# SuperPro-res-moved.net
KiCad netlist of a schematic drawn in EAGLE
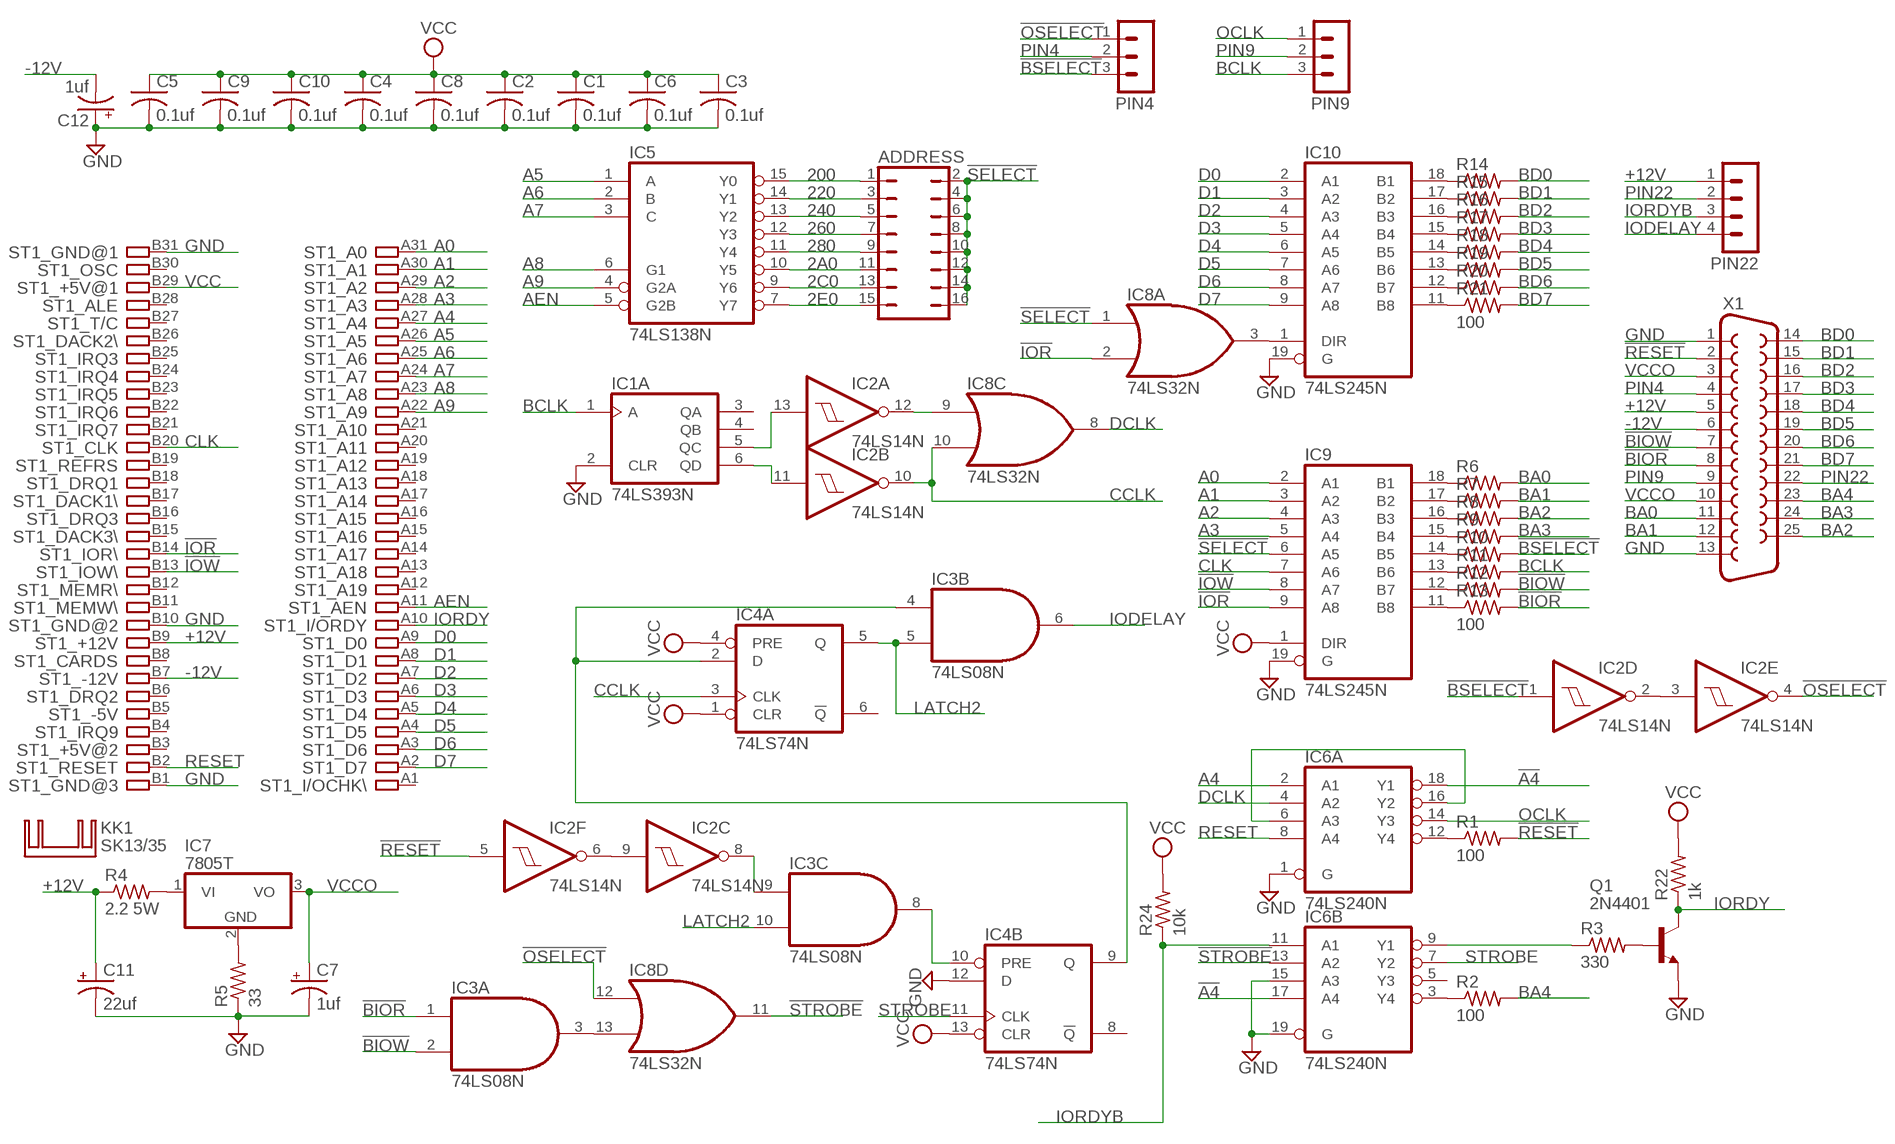
[diagram p0: schematic, sheet 1]

(export (version "E")
  (design (tool "Eeschema 10.0.6"))
  (components
    (comp (ref "ADDRESS")
      (value "JP8Q")
      (footprint "eagle-import:JP8Q")
      (libsource (lib "eagle-import") (part "JP8Q"))
    )
    (comp (ref "C1")
      (value "0.1uf")
      (footprint "eagle-import:C050-025X075")
      (libsource (lib "eagle-import") (part "C-US050-025X075"))
    )
    (comp (ref "C2")
      (value "0.1uf")
      (footprint "eagle-import:C050-025X075")
      (libsource (lib "eagle-import") (part "C-US050-025X075"))
    )
    (comp (ref "C3")
      (value "0.1uf")
      (footprint "eagle-import:C050-025X075")
      (libsource (lib "eagle-import") (part "C-US050-025X075"))
    )
    (comp (ref "C4")
      (value "0.1uf")
      (footprint "eagle-import:C050-025X075")
      (libsource (lib "eagle-import") (part "C-US050-025X075"))
    )
    (comp (ref "C5")
      (value "0.1uf")
      (footprint "eagle-import:C050-025X075")
      (libsource (lib "eagle-import") (part "C-US050-025X075"))
    )
    (comp (ref "C6")
      (value "0.1uf")
      (footprint "eagle-import:C050-025X075")
      (libsource (lib "eagle-import") (part "C-US050-025X075"))
    )
    (comp (ref "C7")
      (value "1uf")
      (footprint "eagle-import:E5-10,5")
      (libsource (lib "eagle-import") (part "CPOL-USE5-10.5"))
    )
    (comp (ref "C8")
      (value "0.1uf")
      (footprint "eagle-import:C050-025X075")
      (libsource (lib "eagle-import") (part "C-US050-025X075"))
    )
    (comp (ref "C9")
      (value "0.1uf")
      (footprint "eagle-import:C050-025X075")
      (libsource (lib "eagle-import") (part "C-US050-025X075"))
    )
    (comp (ref "C10")
      (value "0.1uf")
      (footprint "eagle-import:C050-025X075")
      (libsource (lib "eagle-import") (part "C-US050-025X075"))
    )
    (comp (ref "C11")
      (value "22uf")
      (footprint "eagle-import:E5-10,5")
      (libsource (lib "eagle-import") (part "CPOL-USE5-10.5"))
    )
    (comp (ref "C12")
      (value "1uf")
      (footprint "eagle-import:E5-10,5")
      (libsource (lib "eagle-import") (part "CPOL-USE5-10.5"))
    )
    (comp (ref "IC1")
      (value "74LS393N")
      (footprint "eagle-import:DIL14")
      (libsource (lib "eagle-import") (part "74393NLS"))
    )
    (comp (ref "IC2")
      (value "74LS14N")
      (footprint "eagle-import:DIL14")
      (libsource (lib "eagle-import") (part "7414NLS"))
    )
    (comp (ref "IC3")
      (value "74LS08N")
      (footprint "eagle-import:DIL14")
      (libsource (lib "eagle-import") (part "7408NLS"))
    )
    (comp (ref "IC4")
      (value "74LS74N")
      (footprint "eagle-import:DIL14")
      (libsource (lib "eagle-import") (part "7474NLS"))
    )
    (comp (ref "IC5")
      (value "74LS138N")
      (footprint "eagle-import:DIL16")
      (libsource (lib "eagle-import") (part "74138NLS"))
    )
    (comp (ref "IC6")
      (value "74LS240N")
      (footprint "eagle-import:DIL20")
      (libsource (lib "eagle-import") (part "74240NLS"))
    )
    (comp (ref "IC7")
      (value "7805T")
      (footprint "eagle-import:TO220H")
      (libsource (lib "eagle-import") (part "78T05"))
    )
    (comp (ref "IC8")
      (value "74LS32N")
      (footprint "eagle-import:DIL14")
      (libsource (lib "eagle-import") (part "7432NLS"))
    )
    (comp (ref "IC9")
      (value "74LS245N")
      (footprint "eagle-import:DIL20")
      (libsource (lib "eagle-import") (part "74245NLS"))
    )
    (comp (ref "IC10")
      (value "74LS245N")
      (footprint "eagle-import:DIL20")
      (libsource (lib "eagle-import") (part "74245NLS"))
    )
    (comp (ref "KK1")
      (value "SK13/35")
      (footprint "eagle-import:SK13_35")
      (libsource (lib "eagle-import") (part "SK13/35"))
    )
    (comp (ref "PIN4")
      (value "MA03-1")
      (footprint "eagle-import:MA03-1")
      (libsource (lib "eagle-import") (part "MA03-1"))
    )
    (comp (ref "PIN9")
      (value "MA03-1")
      (footprint "eagle-import:MA03-1")
      (libsource (lib "eagle-import") (part "MA03-1"))
    )
    (comp (ref "PIN22")
      (value "MA04-1")
      (footprint "eagle-import:MA04-1")
      (libsource (lib "eagle-import") (part "MA04-1"))
    )
    (comp (ref "Q1")
      (value "2N4401")
      (footprint "eagle-import:TO92")
      (libsource (lib "eagle-import") (part "2N4416"))
    )
    (comp (ref "R1")
      (value "100")
      (footprint "eagle-import:0207_10")
      (libsource (lib "eagle-import") (part "R-US_0207/10"))
    )
    (comp (ref "R2")
      (value "100")
      (footprint "eagle-import:0207_10")
      (libsource (lib "eagle-import") (part "R-US_0207/10"))
    )
    (comp (ref "R3")
      (value "330")
      (footprint "eagle-import:0207_10")
      (libsource (lib "eagle-import") (part "R-US_0207/10"))
    )
    (comp (ref "R4")
      (value "2.2 5W")
      (footprint "eagle-import:0922_22")
      (libsource (lib "eagle-import") (part "R-US_0922/22"))
    )
    (comp (ref "R5")
      (value "33")
      (footprint "eagle-import:0207_10")
      (libsource (lib "eagle-import") (part "R-US_0207/10"))
    )
    (comp (ref "R6")
      (value "R-US_0207/10")
      (footprint "eagle-import:0207_10")
      (libsource (lib "eagle-import") (part "R-US_0207/10"))
    )
    (comp (ref "R7")
      (value "R-US_0207/10")
      (footprint "eagle-import:0207_10")
      (libsource (lib "eagle-import") (part "R-US_0207/10"))
    )
    (comp (ref "R8")
      (value "R-US_0207/10")
      (footprint "eagle-import:0207_10")
      (libsource (lib "eagle-import") (part "R-US_0207/10"))
    )
    (comp (ref "R9")
      (value "R-US_0207/10")
      (footprint "eagle-import:0207_10")
      (libsource (lib "eagle-import") (part "R-US_0207/10"))
    )
    (comp (ref "R10")
      (value "R-US_0207/10")
      (footprint "eagle-import:0207_10")
      (libsource (lib "eagle-import") (part "R-US_0207/10"))
    )
    (comp (ref "R11")
      (value "R-US_0207/10")
      (footprint "eagle-import:0207_10")
      (libsource (lib "eagle-import") (part "R-US_0207/10"))
    )
    (comp (ref "R12")
      (value "R-US_0207/10")
      (footprint "eagle-import:0207_10")
      (libsource (lib "eagle-import") (part "R-US_0207/10"))
    )
    (comp (ref "R13")
      (value "100")
      (footprint "eagle-import:0207_10")
      (libsource (lib "eagle-import") (part "R-US_0207/10"))
    )
    (comp (ref "R14")
      (value "R-US_0207/10")
      (footprint "eagle-import:0207_10")
      (libsource (lib "eagle-import") (part "R-US_0207/10"))
    )
    (comp (ref "R15")
      (value "R-US_0207/10")
      (footprint "eagle-import:0207_10")
      (libsource (lib "eagle-import") (part "R-US_0207/10"))
    )
    (comp (ref "R16")
      (value "R-US_0207/10")
      (footprint "eagle-import:0207_10")
      (libsource (lib "eagle-import") (part "R-US_0207/10"))
    )
    (comp (ref "R17")
      (value "R-US_0207/10")
      (footprint "eagle-import:0207_10")
      (libsource (lib "eagle-import") (part "R-US_0207/10"))
    )
    (comp (ref "R18")
      (value "R-US_0207/10")
      (footprint "eagle-import:0207_10")
      (libsource (lib "eagle-import") (part "R-US_0207/10"))
    )
    (comp (ref "R19")
      (value "R-US_0207/10")
      (footprint "eagle-import:0207_10")
      (libsource (lib "eagle-import") (part "R-US_0207/10"))
    )
    (comp (ref "R20")
      (value "R-US_0207/10")
      (footprint "eagle-import:0207_10")
      (libsource (lib "eagle-import") (part "R-US_0207/10"))
    )
    (comp (ref "R21")
      (value "100")
      (footprint "eagle-import:0207_10")
      (libsource (lib "eagle-import") (part "R-US_0207/10"))
    )
    (comp (ref "R22")
      (value "1k")
      (footprint "eagle-import:0207_10")
      (libsource (lib "eagle-import") (part "R-US_0207/10"))
    )
    (comp (ref "R24")
      (value "10k")
      (footprint "eagle-import:0207_10")
      (libsource (lib "eagle-import") (part "R-US_0207/10"))
    )
    (comp (ref "ST1")
      (value "IBM8BIT")
      (footprint "eagle-import:IBM8BIT")
      (libsource (lib "eagle-import") (part "IBM8BIT"))
    )
    (comp (ref "X1")
      (value "F25H")
      (footprint "eagle-import:F25H")
      (libsource (lib "eagle-import") (part "F25H"))
    )
  )
  (nets
    (net (code "1") (name "/+12V") (class "Default")
      (node (ref "C11") (pin "+") (pinfunction "+_+") (pintype "passive"))
      (node (ref "PIN22") (pin "1") (pinfunction "1_1") (pintype "passive"))
      (node (ref "R4") (pin "1") (pinfunction "1_1") (pintype "passive"))
      (node (ref "ST1") (pin "B9") (pinfunction "P_B9") (pintype "bidirectional"))
      (node (ref "X1") (pin "5") (pinfunction "5_5") (pintype "passive"))
    )
    (net (code "2") (name "/-12V") (class "Default")
      (node (ref "C12") (pin "-") (pinfunction "-_-") (pintype "passive"))
      (node (ref "ST1") (pin "B7") (pinfunction "P_B7") (pintype "bidirectional"))
      (node (ref "X1") (pin "6") (pinfunction "6_6") (pintype "passive"))
    )
    (net (code "3") (name "/2A0") (class "Default")
      (node (ref "ADDRESS") (pin "11") (pinfunction "11_11") (pintype "passive"))
      (node (ref "IC5") (pin "10") (pinfunction "Y5_10") (pintype "output"))
    )
    (net (code "4") (name "/2C0") (class "Default")
      (node (ref "ADDRESS") (pin "13") (pinfunction "13_13") (pintype "passive"))
      (node (ref "IC5") (pin "9") (pinfunction "Y6_9") (pintype "output"))
    )
    (net (code "5") (name "/2E0") (class "Default")
      (node (ref "ADDRESS") (pin "15") (pinfunction "15_15") (pintype "passive"))
      (node (ref "IC5") (pin "7") (pinfunction "Y7_7") (pintype "output"))
    )
    (net (code "6") (name "/200") (class "Default")
      (node (ref "ADDRESS") (pin "1") (pinfunction "1_1") (pintype "passive"))
      (node (ref "IC5") (pin "15") (pinfunction "Y0_15") (pintype "output"))
    )
    (net (code "7") (name "/220") (class "Default")
      (node (ref "ADDRESS") (pin "3") (pinfunction "3_3") (pintype "passive"))
      (node (ref "IC5") (pin "14") (pinfunction "Y1_14") (pintype "output"))
    )
    (net (code "8") (name "/240") (class "Default")
      (node (ref "ADDRESS") (pin "5") (pinfunction "5_5") (pintype "passive"))
      (node (ref "IC5") (pin "13") (pinfunction "Y2_13") (pintype "output"))
    )
    (net (code "9") (name "/260") (class "Default")
      (node (ref "ADDRESS") (pin "7") (pinfunction "7_7") (pintype "passive"))
      (node (ref "IC5") (pin "12") (pinfunction "Y3_12") (pintype "output"))
    )
    (net (code "10") (name "/280") (class "Default")
      (node (ref "ADDRESS") (pin "9") (pinfunction "9_9") (pintype "passive"))
      (node (ref "IC5") (pin "11") (pinfunction "Y4_11") (pintype "output"))
    )
    (net (code "11") (name "/A0") (class "Default")
      (node (ref "IC9") (pin "2") (pinfunction "A1_2") (pintype "bidirectional"))
      (node (ref "ST1") (pin "A31") (pinfunction "P_A31") (pintype "bidirectional"))
    )
    (net (code "12") (name "/A1") (class "Default")
      (node (ref "IC9") (pin "3") (pinfunction "A2_3") (pintype "bidirectional"))
      (node (ref "ST1") (pin "A30") (pinfunction "P_A30") (pintype "bidirectional"))
    )
    (net (code "13") (name "/A2") (class "Default")
      (node (ref "IC9") (pin "4") (pinfunction "A3_4") (pintype "bidirectional"))
      (node (ref "ST1") (pin "A29") (pinfunction "P_A29") (pintype "bidirectional"))
    )
    (net (code "14") (name "/A3") (class "Default")
      (node (ref "IC9") (pin "5") (pinfunction "A4_5") (pintype "bidirectional"))
      (node (ref "ST1") (pin "A28") (pinfunction "P_A28") (pintype "bidirectional"))
    )
    (net (code "15") (name "/A4") (class "Default")
      (node (ref "IC6") (pin "2") (pinfunction "A1_2") (pintype "input"))
      (node (ref "ST1") (pin "A27") (pinfunction "P_A27") (pintype "bidirectional"))
    )
    (net (code "16") (name "/A5") (class "Default")
      (node (ref "IC5") (pin "1") (pinfunction "A_1") (pintype "input"))
      (node (ref "ST1") (pin "A26") (pinfunction "P_A26") (pintype "bidirectional"))
    )
    (net (code "17") (name "/A6") (class "Default")
      (node (ref "IC5") (pin "2") (pinfunction "B_2") (pintype "input"))
      (node (ref "ST1") (pin "A25") (pinfunction "P_A25") (pintype "bidirectional"))
    )
    (net (code "18") (name "/A7") (class "Default")
      (node (ref "IC5") (pin "3") (pinfunction "C_3") (pintype "input"))
      (node (ref "ST1") (pin "A24") (pinfunction "P_A24") (pintype "bidirectional"))
    )
    (net (code "19") (name "/A8") (class "Default")
      (node (ref "IC5") (pin "6") (pinfunction "G1_6") (pintype "input"))
      (node (ref "ST1") (pin "A23") (pinfunction "P_A23") (pintype "bidirectional"))
    )
    (net (code "20") (name "/A9") (class "Default")
      (node (ref "IC5") (pin "4") (pinfunction "G2A_4") (pintype "input"))
      (node (ref "ST1") (pin "A22") (pinfunction "P_A22") (pintype "bidirectional"))
    )
    (net (code "21") (name "/AEN") (class "Default")
      (node (ref "IC5") (pin "5") (pinfunction "G2B_5") (pintype "input"))
      (node (ref "ST1") (pin "A11") (pinfunction "P_A11") (pintype "bidirectional"))
    )
    (net (code "22") (name "/BA0") (class "Default")
      (node (ref "R6") (pin "2") (pinfunction "2_2") (pintype "passive"))
      (node (ref "X1") (pin "11") (pinfunction "11_11") (pintype "passive"))
    )
    (net (code "23") (name "/BA1") (class "Default")
      (node (ref "R7") (pin "2") (pinfunction "2_2") (pintype "passive"))
      (node (ref "X1") (pin "12") (pinfunction "12_12") (pintype "passive"))
    )
    (net (code "24") (name "/BA2") (class "Default")
      (node (ref "R8") (pin "2") (pinfunction "2_2") (pintype "passive"))
      (node (ref "X1") (pin "25") (pinfunction "25_25") (pintype "passive"))
    )
    (net (code "25") (name "/BA3") (class "Default")
      (node (ref "R9") (pin "2") (pinfunction "2_2") (pintype "passive"))
      (node (ref "X1") (pin "24") (pinfunction "24_24") (pintype "passive"))
    )
    (net (code "26") (name "/BA4") (class "Default")
      (node (ref "R2") (pin "2") (pinfunction "2_2") (pintype "passive"))
      (node (ref "X1") (pin "23") (pinfunction "23_23") (pintype "passive"))
    )
    (net (code "27") (name "/BCLK") (class "Default")
      (node (ref "IC1") (pin "1") (pinfunction "A_1") (pintype "input"))
      (node (ref "PIN9") (pin "3") (pinfunction "3_3") (pintype "passive"))
      (node (ref "R11") (pin "2") (pinfunction "2_2") (pintype "passive"))
    )
    (net (code "28") (name "/BD0") (class "Default")
      (node (ref "R14") (pin "2") (pinfunction "2_2") (pintype "passive"))
      (node (ref "X1") (pin "14") (pinfunction "14_14") (pintype "passive"))
    )
    (net (code "29") (name "/BD1") (class "Default")
      (node (ref "R15") (pin "2") (pinfunction "2_2") (pintype "passive"))
      (node (ref "X1") (pin "15") (pinfunction "15_15") (pintype "passive"))
    )
    (net (code "30") (name "/BD2") (class "Default")
      (node (ref "R16") (pin "2") (pinfunction "2_2") (pintype "passive"))
      (node (ref "X1") (pin "16") (pinfunction "16_16") (pintype "passive"))
    )
    (net (code "31") (name "/BD3") (class "Default")
      (node (ref "R17") (pin "2") (pinfunction "2_2") (pintype "passive"))
      (node (ref "X1") (pin "17") (pinfunction "17_17") (pintype "passive"))
    )
    (net (code "32") (name "/BD4") (class "Default")
      (node (ref "R18") (pin "2") (pinfunction "2_2") (pintype "passive"))
      (node (ref "X1") (pin "18") (pinfunction "18_18") (pintype "passive"))
    )
    (net (code "33") (name "/BD5") (class "Default")
      (node (ref "R19") (pin "2") (pinfunction "2_2") (pintype "passive"))
      (node (ref "X1") (pin "19") (pinfunction "19_19") (pintype "passive"))
    )
    (net (code "34") (name "/BD6") (class "Default")
      (node (ref "R20") (pin "2") (pinfunction "2_2") (pintype "passive"))
      (node (ref "X1") (pin "20") (pinfunction "20_20") (pintype "passive"))
    )
    (net (code "35") (name "/BD7") (class "Default")
      (node (ref "R21") (pin "2") (pinfunction "2_2") (pintype "passive"))
      (node (ref "X1") (pin "21") (pinfunction "21_21") (pintype "passive"))
    )
    (net (code "36") (name "/CCLK") (class "Default")
      (node (ref "IC2") (pin "10") (pinfunction "O_10") (pintype "output"))
      (node (ref "IC4") (pin "3") (pinfunction "CLK_3") (pintype "input"))
      (node (ref "IC8") (pin "10") (pinfunction "I1_10") (pintype "input"))
    )
    (net (code "37") (name "/CLK") (class "Default")
      (node (ref "IC9") (pin "7") (pinfunction "A6_7") (pintype "bidirectional"))
      (node (ref "ST1") (pin "B20") (pinfunction "P_B20") (pintype "bidirectional"))
    )
    (net (code "38") (name "/D0") (class "Default")
      (node (ref "IC10") (pin "2") (pinfunction "A1_2") (pintype "bidirectional"))
      (node (ref "ST1") (pin "A9") (pinfunction "P_A9") (pintype "bidirectional"))
    )
    (net (code "39") (name "/D1") (class "Default")
      (node (ref "IC10") (pin "3") (pinfunction "A2_3") (pintype "bidirectional"))
      (node (ref "ST1") (pin "A8") (pinfunction "P_A8") (pintype "bidirectional"))
    )
    (net (code "40") (name "/D2") (class "Default")
      (node (ref "IC10") (pin "4") (pinfunction "A3_4") (pintype "bidirectional"))
      (node (ref "ST1") (pin "A7") (pinfunction "P_A7") (pintype "bidirectional"))
    )
    (net (code "41") (name "/D3") (class "Default")
      (node (ref "IC10") (pin "5") (pinfunction "A4_5") (pintype "bidirectional"))
      (node (ref "ST1") (pin "A6") (pinfunction "P_A6") (pintype "bidirectional"))
    )
    (net (code "42") (name "/D4") (class "Default")
      (node (ref "IC10") (pin "6") (pinfunction "A5_6") (pintype "bidirectional"))
      (node (ref "ST1") (pin "A5") (pinfunction "P_A5") (pintype "bidirectional"))
    )
    (net (code "43") (name "/D5") (class "Default")
      (node (ref "IC10") (pin "7") (pinfunction "A6_7") (pintype "bidirectional"))
      (node (ref "ST1") (pin "A4") (pinfunction "P_A4") (pintype "bidirectional"))
    )
    (net (code "44") (name "/D6") (class "Default")
      (node (ref "IC10") (pin "8") (pinfunction "A7_8") (pintype "bidirectional"))
      (node (ref "ST1") (pin "A3") (pinfunction "P_A3") (pintype "bidirectional"))
    )
    (net (code "45") (name "/D7") (class "Default")
      (node (ref "IC10") (pin "9") (pinfunction "A8_9") (pintype "bidirectional"))
      (node (ref "ST1") (pin "A2") (pinfunction "P_A2") (pintype "bidirectional"))
    )
    (net (code "46") (name "/DCLK") (class "Default")
      (node (ref "IC6") (pin "4") (pinfunction "A2_4") (pintype "input"))
      (node (ref "IC8") (pin "8") (pinfunction "O_8") (pintype "output"))
    )
    (net (code "47") (name "/IODELAY") (class "Default")
      (node (ref "IC3") (pin "6") (pinfunction "O_6") (pintype "output"))
      (node (ref "PIN22") (pin "4") (pinfunction "4_4") (pintype "passive"))
    )
    (net (code "48") (name "/IORDY") (class "Default")
      (node (ref "Q1") (pin "1") (pinfunction "C_1") (pintype "passive"))
      (node (ref "R22") (pin "1") (pinfunction "1_1") (pintype "passive"))
      (node (ref "ST1") (pin "A10") (pinfunction "P_A10") (pintype "bidirectional"))
    )
    (net (code "49") (name "/IORDYB") (class "Default")
      (node (ref "IC6") (pin "11") (pinfunction "A1_11") (pintype "input"))
      (node (ref "PIN22") (pin "3") (pinfunction "3_3") (pintype "passive"))
      (node (ref "R24") (pin "1") (pinfunction "1_1") (pintype "passive"))
    )
    (net (code "50") (name "/LATCH2") (class "Default")
      (node (ref "IC3") (pin "10") (pinfunction "I1_10") (pintype "input"))
      (node (ref "IC3") (pin "5") (pinfunction "I1_5") (pintype "input"))
      (node (ref "IC4") (pin "5") (pinfunction "Q_5") (pintype "output"))
    )
    (net (code "51") (name "/OCLK") (class "Default")
      (node (ref "IC6") (pin "14") (pinfunction "Y3_14") (pintype "tri_state"))
      (node (ref "PIN9") (pin "1") (pinfunction "1_1") (pintype "passive"))
    )
    (net (code "52") (name "/PIN4") (class "Default")
      (node (ref "PIN4") (pin "2") (pinfunction "2_2") (pintype "passive"))
      (node (ref "X1") (pin "4") (pinfunction "4_4") (pintype "passive"))
    )
    (net (code "53") (name "/PIN9") (class "Default")
      (node (ref "PIN9") (pin "2") (pinfunction "2_2") (pintype "passive"))
      (node (ref "X1") (pin "9") (pinfunction "9_9") (pintype "passive"))
    )
    (net (code "54") (name "/PIN22") (class "Default")
      (node (ref "PIN22") (pin "2") (pinfunction "2_2") (pintype "passive"))
      (node (ref "X1") (pin "22") (pinfunction "22_22") (pintype "passive"))
    )
    (net (code "55") (name "/RESET") (class "Default")
      (node (ref "IC6") (pin "8") (pinfunction "A4_8") (pintype "input"))
      (node (ref "ST1") (pin "B2") (pinfunction "P_B2") (pintype "bidirectional"))
    )
    (net (code "56") (name "/STROBE") (class "Default")
      (node (ref "IC4") (pin "11") (pinfunction "CLK_11") (pintype "input"))
      (node (ref "IC6") (pin "7") (pinfunction "Y2_7") (pintype "tri_state"))
    )
    (net (code "57") (name "/VCCO") (class "Default")
      (node (ref "C7") (pin "+") (pinfunction "+_+") (pintype "passive"))
      (node (ref "IC7") (pin "3") (pinfunction "VO_3") (pintype "passive"))
      (node (ref "X1") (pin "10") (pinfunction "10_10") (pintype "passive"))
      (node (ref "X1") (pin "3") (pinfunction "3_3") (pintype "passive"))
    )
    (net (code "58") (name "/~{A4}") (class "Default")
      (node (ref "IC6") (pin "17") (pinfunction "A4_17") (pintype "input"))
      (node (ref "IC6") (pin "18") (pinfunction "Y1_18") (pintype "tri_state"))
    )
    (net (code "59") (name "/~{BIOR}") (class "Default")
      (node (ref "IC3") (pin "1") (pinfunction "I0_1") (pintype "input"))
      (node (ref "R13") (pin "2") (pinfunction "2_2") (pintype "passive"))
      (node (ref "X1") (pin "8") (pinfunction "8_8") (pintype "passive"))
    )
    (net (code "60") (name "/~{BIOW}") (class "Default")
      (node (ref "IC3") (pin "2") (pinfunction "I1_2") (pintype "input"))
      (node (ref "R12") (pin "2") (pinfunction "2_2") (pintype "passive"))
      (node (ref "X1") (pin "7") (pinfunction "7_7") (pintype "passive"))
    )
    (net (code "61") (name "/~{BSELECT}") (class "Default")
      (node (ref "IC2") (pin "1") (pinfunction "I_1") (pintype "input"))
      (node (ref "PIN4") (pin "3") (pinfunction "3_3") (pintype "passive"))
      (node (ref "R10") (pin "2") (pinfunction "2_2") (pintype "passive"))
    )
    (net (code "62") (name "/~{IOR}") (class "Default")
      (node (ref "IC8") (pin "2") (pinfunction "I1_2") (pintype "input"))
      (node (ref "IC9") (pin "9") (pinfunction "A8_9") (pintype "bidirectional"))
      (node (ref "ST1") (pin "B14") (pinfunction "P_B14") (pintype "bidirectional"))
    )
    (net (code "63") (name "/~{IOW}") (class "Default")
      (node (ref "IC9") (pin "8") (pinfunction "A7_8") (pintype "bidirectional"))
      (node (ref "ST1") (pin "B13") (pinfunction "P_B13") (pintype "bidirectional"))
    )
    (net (code "64") (name "/~{OSELECT}") (class "Default")
      (node (ref "IC2") (pin "4") (pinfunction "O_4") (pintype "output"))
      (node (ref "IC8") (pin "12") (pinfunction "I0_12") (pintype "input"))
      (node (ref "PIN4") (pin "1") (pinfunction "1_1") (pintype "passive"))
    )
    (net (code "65") (name "/~{RESET}") (class "Default")
      (node (ref "IC2") (pin "5") (pinfunction "I_5") (pintype "input"))
      (node (ref "R1") (pin "2") (pinfunction "2_2") (pintype "passive"))
      (node (ref "X1") (pin "2") (pinfunction "2_2") (pintype "passive"))
    )
    (net (code "66") (name "/~{SELECT}") (class "Default")
      (node (ref "ADDRESS") (pin "10") (pinfunction "10_10") (pintype "passive"))
      (node (ref "ADDRESS") (pin "12") (pinfunction "12_12") (pintype "passive"))
      (node (ref "ADDRESS") (pin "14") (pinfunction "14_14") (pintype "passive"))
      (node (ref "ADDRESS") (pin "16") (pinfunction "16_16") (pintype "passive"))
      (node (ref "ADDRESS") (pin "2") (pinfunction "2_2") (pintype "passive"))
      (node (ref "ADDRESS") (pin "4") (pinfunction "4_4") (pintype "passive"))
      (node (ref "ADDRESS") (pin "6") (pinfunction "6_6") (pintype "passive"))
      (node (ref "ADDRESS") (pin "8") (pinfunction "8_8") (pintype "passive"))
      (node (ref "IC8") (pin "1") (pinfunction "I0_1") (pintype "input"))
      (node (ref "IC9") (pin "6") (pinfunction "A5_6") (pintype "bidirectional"))
    )
    (net (code "67") (name "/~{STROBE}") (class "Default")
      (node (ref "IC6") (pin "13") (pinfunction "A2_13") (pintype "input"))
      (node (ref "IC8") (pin "11") (pinfunction "O_11") (pintype "output"))
    )
    (net (code "68") (name "GND") (class "Default")
      (node (ref "C1") (pin "2") (pinfunction "2_2") (pintype "passive"))
      (node (ref "C10") (pin "2") (pinfunction "2_2") (pintype "passive"))
      (node (ref "C11") (pin "-") (pinfunction "-_-") (pintype "passive"))
      (node (ref "C12") (pin "+") (pinfunction "+_+") (pintype "passive"))
      (node (ref "C2") (pin "2") (pinfunction "2_2") (pintype "passive"))
      (node (ref "C3") (pin "2") (pinfunction "2_2") (pintype "passive"))
      (node (ref "C4") (pin "2") (pinfunction "2_2") (pintype "passive"))
      (node (ref "C5") (pin "2") (pinfunction "2_2") (pintype "passive"))
      (node (ref "C6") (pin "2") (pinfunction "2_2") (pintype "passive"))
      (node (ref "C7") (pin "-") (pinfunction "-_-") (pintype "passive"))
      (node (ref "C8") (pin "2") (pinfunction "2_2") (pintype "passive"))
      (node (ref "C9") (pin "2") (pinfunction "2_2") (pintype "passive"))
      (node (ref "IC1") (pin "2") (pinfunction "CLR_2") (pintype "input"))
      (node (ref "IC10") (pin "19") (pinfunction "G_19") (pintype "input"))
      (node (ref "IC4") (pin "12") (pinfunction "D_12") (pintype "input"))
      (node (ref "IC6") (pin "1") (pinfunction "G_1") (pintype "input"))
      (node (ref "IC6") (pin "15") (pinfunction "A3_15") (pintype "input"))
      (node (ref "IC6") (pin "19") (pinfunction "G_19") (pintype "input"))
      (node (ref "IC9") (pin "19") (pinfunction "G_19") (pintype "input"))
      (node (ref "Q1") (pin "3") (pinfunction "E_3") (pintype "passive"))
      (node (ref "R5") (pin "1") (pinfunction "1_1") (pintype "passive"))
      (node (ref "ST1") (pin "B1") (pinfunction "P_B1") (pintype "bidirectional"))
      (node (ref "ST1") (pin "B10") (pinfunction "P_B10") (pintype "bidirectional"))
      (node (ref "ST1") (pin "B31") (pinfunction "P_B31") (pintype "bidirectional"))
      (node (ref "X1") (pin "1") (pinfunction "1_1") (pintype "passive"))
      (node (ref "X1") (pin "13") (pinfunction "13_13") (pintype "passive"))
    )
    (net (code "69") (name "Net-(IC1A-QC)") (class "Default")
      (node (ref "IC1") (pin "5") (pinfunction "QC_5") (pintype "output"))
      (node (ref "IC2") (pin "13") (pinfunction "I_13") (pintype "input"))
    )
    (net (code "70") (name "Net-(IC1A-QD)") (class "Default")
      (node (ref "IC1") (pin "6") (pinfunction "QD_6") (pintype "output"))
      (node (ref "IC2") (pin "11") (pinfunction "I_11") (pintype "input"))
    )
    (net (code "71") (name "Net-(IC2A-O)") (class "Default")
      (node (ref "IC2") (pin "12") (pinfunction "O_12") (pintype "output"))
      (node (ref "IC8") (pin "9") (pinfunction "I0_9") (pintype "input"))
    )
    (net (code "72") (name "Net-(IC2C-I)") (class "Default")
      (node (ref "IC2") (pin "6") (pinfunction "O_6") (pintype "output"))
      (node (ref "IC2") (pin "9") (pinfunction "I_9") (pintype "input"))
    )
    (net (code "73") (name "Net-(IC2C-O)") (class "Default")
      (node (ref "IC2") (pin "8") (pinfunction "O_8") (pintype "output"))
      (node (ref "IC3") (pin "9") (pinfunction "I0_9") (pintype "input"))
    )
    (net (code "74") (name "Net-(IC2D-O)") (class "Default")
      (node (ref "IC2") (pin "2") (pinfunction "O_2") (pintype "output"))
      (node (ref "IC2") (pin "3") (pinfunction "I_3") (pintype "input"))
    )
    (net (code "75") (name "Net-(IC3A-O)") (class "Default")
      (node (ref "IC3") (pin "3") (pinfunction "O_3") (pintype "output"))
      (node (ref "IC8") (pin "13") (pinfunction "I1_13") (pintype "input"))
    )
    (net (code "76") (name "Net-(IC3B-I0)") (class "Default")
      (node (ref "IC3") (pin "4") (pinfunction "I0_4") (pintype "input"))
      (node (ref "IC4") (pin "2") (pinfunction "D_2") (pintype "input"))
      (node (ref "IC4") (pin "9") (pinfunction "Q_9") (pintype "output"))
    )
    (net (code "77") (name "Net-(IC3C-O)") (class "Default")
      (node (ref "IC3") (pin "8") (pinfunction "O_8") (pintype "output"))
      (node (ref "IC4") (pin "10") (pinfunction "PRE_10") (pintype "input"))
    )
    (net (code "78") (name "Net-(IC6A-A3)") (class "Default")
      (node (ref "IC6") (pin "16") (pinfunction "Y2_16") (pintype "tri_state"))
      (node (ref "IC6") (pin "6") (pinfunction "A3_6") (pintype "input"))
    )
    (net (code "79") (name "Net-(IC6A-Y4)") (class "Default")
      (node (ref "IC6") (pin "12") (pinfunction "Y4_12") (pintype "tri_state"))
      (node (ref "R1") (pin "1") (pinfunction "1_1") (pintype "passive"))
    )
    (net (code "80") (name "Net-(IC6B-Y1)") (class "Default")
      (node (ref "IC6") (pin "9") (pinfunction "Y1_9") (pintype "tri_state"))
      (node (ref "R3") (pin "1") (pinfunction "1_1") (pintype "passive"))
    )
    (net (code "81") (name "Net-(IC6B-Y4)") (class "Default")
      (node (ref "IC6") (pin "3") (pinfunction "Y4_3") (pintype "tri_state"))
      (node (ref "R2") (pin "1") (pinfunction "1_1") (pintype "passive"))
    )
    (net (code "82") (name "Net-(IC7-GND)") (class "Default")
      (node (ref "IC7") (pin "2") (pinfunction "GND_2") (pintype "passive"))
      (node (ref "R5") (pin "2") (pinfunction "2_2") (pintype "passive"))
    )
    (net (code "83") (name "Net-(IC7-VI)") (class "Default")
      (node (ref "IC7") (pin "1") (pinfunction "VI_1") (pintype "input"))
      (node (ref "R4") (pin "2") (pinfunction "2_2") (pintype "passive"))
    )
    (net (code "84") (name "Net-(IC9A-B1)") (class "Default")
      (node (ref "IC9") (pin "18") (pinfunction "B1_18") (pintype "bidirectional"))
      (node (ref "R6") (pin "1") (pinfunction "1_1") (pintype "passive"))
    )
    (net (code "85") (name "Net-(IC9A-B2)") (class "Default")
      (node (ref "IC9") (pin "17") (pinfunction "B2_17") (pintype "bidirectional"))
      (node (ref "R7") (pin "1") (pinfunction "1_1") (pintype "passive"))
    )
    (net (code "86") (name "Net-(IC9A-B3)") (class "Default")
      (node (ref "IC9") (pin "16") (pinfunction "B3_16") (pintype "bidirectional"))
      (node (ref "R8") (pin "1") (pinfunction "1_1") (pintype "passive"))
    )
    (net (code "87") (name "Net-(IC9A-B4)") (class "Default")
      (node (ref "IC9") (pin "15") (pinfunction "B4_15") (pintype "bidirectional"))
      (node (ref "R9") (pin "1") (pinfunction "1_1") (pintype "passive"))
    )
    (net (code "88") (name "Net-(IC9A-B5)") (class "Default")
      (node (ref "IC9") (pin "14") (pinfunction "B5_14") (pintype "bidirectional"))
      (node (ref "R10") (pin "1") (pinfunction "1_1") (pintype "passive"))
    )
    (net (code "89") (name "Net-(IC9A-B6)") (class "Default")
      (node (ref "IC9") (pin "13") (pinfunction "B6_13") (pintype "bidirectional"))
      (node (ref "R11") (pin "1") (pinfunction "1_1") (pintype "passive"))
    )
    (net (code "90") (name "Net-(IC9A-B7)") (class "Default")
      (node (ref "IC9") (pin "12") (pinfunction "B7_12") (pintype "bidirectional"))
      (node (ref "R12") (pin "1") (pinfunction "1_1") (pintype "passive"))
    )
    (net (code "91") (name "Net-(IC9A-B8)") (class "Default")
      (node (ref "IC9") (pin "11") (pinfunction "B8_11") (pintype "bidirectional"))
      (node (ref "R13") (pin "1") (pinfunction "1_1") (pintype "passive"))
    )
    (net (code "92") (name "Net-(IC10A-B1)") (class "Default")
      (node (ref "IC10") (pin "18") (pinfunction "B1_18") (pintype "bidirectional"))
      (node (ref "R14") (pin "1") (pinfunction "1_1") (pintype "passive"))
    )
    (net (code "93") (name "Net-(IC10A-B2)") (class "Default")
      (node (ref "IC10") (pin "17") (pinfunction "B2_17") (pintype "bidirectional"))
      (node (ref "R15") (pin "1") (pinfunction "1_1") (pintype "passive"))
    )
    (net (code "94") (name "Net-(IC10A-B3)") (class "Default")
      (node (ref "IC10") (pin "16") (pinfunction "B3_16") (pintype "bidirectional"))
      (node (ref "R16") (pin "1") (pinfunction "1_1") (pintype "passive"))
    )
    (net (code "95") (name "Net-(IC10A-B4)") (class "Default")
      (node (ref "IC10") (pin "15") (pinfunction "B4_15") (pintype "bidirectional"))
      (node (ref "R17") (pin "1") (pinfunction "1_1") (pintype "passive"))
    )
    (net (code "96") (name "Net-(IC10A-B5)") (class "Default")
      (node (ref "IC10") (pin "14") (pinfunction "B5_14") (pintype "bidirectional"))
      (node (ref "R18") (pin "1") (pinfunction "1_1") (pintype "passive"))
    )
    (net (code "97") (name "Net-(IC10A-B6)") (class "Default")
      (node (ref "IC10") (pin "13") (pinfunction "B6_13") (pintype "bidirectional"))
      (node (ref "R19") (pin "1") (pinfunction "1_1") (pintype "passive"))
    )
    (net (code "98") (name "Net-(IC10A-B7)") (class "Default")
      (node (ref "IC10") (pin "12") (pinfunction "B7_12") (pintype "bidirectional"))
      (node (ref "R20") (pin "1") (pinfunction "1_1") (pintype "passive"))
    )
    (net (code "99") (name "Net-(IC10A-B8)") (class "Default")
      (node (ref "IC10") (pin "11") (pinfunction "B8_11") (pintype "bidirectional"))
      (node (ref "R21") (pin "1") (pinfunction "1_1") (pintype "passive"))
    )
    (net (code "100") (name "Net-(IC10A-DIR)") (class "Default")
      (node (ref "IC10") (pin "1") (pinfunction "DIR_1") (pintype "input"))
      (node (ref "IC8") (pin "3") (pinfunction "O_3") (pintype "output"))
    )
    (net (code "101") (name "Net-(Q1-B)") (class "Default")
      (node (ref "Q1") (pin "2") (pinfunction "B_2") (pintype "passive"))
      (node (ref "R3") (pin "2") (pinfunction "2_2") (pintype "passive"))
    )
    (net (code "102") (name "VCC") (class "Default")
      (node (ref "C1") (pin "1") (pinfunction "1_1") (pintype "passive"))
      (node (ref "C10") (pin "1") (pinfunction "1_1") (pintype "passive"))
      (node (ref "C2") (pin "1") (pinfunction "1_1") (pintype "passive"))
      (node (ref "C3") (pin "1") (pinfunction "1_1") (pintype "passive"))
      (node (ref "C4") (pin "1") (pinfunction "1_1") (pintype "passive"))
      (node (ref "C5") (pin "1") (pinfunction "1_1") (pintype "passive"))
      (node (ref "C6") (pin "1") (pinfunction "1_1") (pintype "passive"))
      (node (ref "C8") (pin "1") (pinfunction "1_1") (pintype "passive"))
      (node (ref "C9") (pin "1") (pinfunction "1_1") (pintype "passive"))
      (node (ref "IC4") (pin "1") (pinfunction "CLR_1") (pintype "input"))
      (node (ref "IC4") (pin "13") (pinfunction "CLR_13") (pintype "input"))
      (node (ref "IC4") (pin "4") (pinfunction "PRE_4") (pintype "input"))
      (node (ref "IC9") (pin "1") (pinfunction "DIR_1") (pintype "input"))
      (node (ref "R22") (pin "2") (pinfunction "2_2") (pintype "passive"))
      (node (ref "R24") (pin "2") (pinfunction "2_2") (pintype "passive"))
      (node (ref "ST1") (pin "B29") (pinfunction "P_B29") (pintype "bidirectional"))
    )
    (net (code "103") (name "unconnected-(IC1A-QA-Pad3)") (class "Default")
      (node (ref "IC1") (pin "3") (pinfunction "QA_3") (pintype "output"))
    )
    (net (code "104") (name "unconnected-(IC1A-QB-Pad4)") (class "Default")
      (node (ref "IC1") (pin "4") (pinfunction "QB_4") (pintype "output"))
    )
    (net (code "105") (name "unconnected-(IC4A-~{Q}-Pad6)") (class "Default")
      (node (ref "IC4") (pin "6") (pinfunction "~{Q}_6") (pintype "output"))
    )
    (net (code "106") (name "unconnected-(IC4B-~{Q}-Pad8)") (class "Default")
      (node (ref "IC4") (pin "8") (pinfunction "~{Q}_8") (pintype "output"))
    )
    (net (code "107") (name "unconnected-(IC6B-Y3-Pad5)") (class "Default")
      (node (ref "IC6") (pin "5") (pinfunction "Y3_5") (pintype "tri_state"))
    )
    (net (code "108") (name "unconnected-(ST1AA-P-PadB28)") (class "Default")
      (node (ref "ST1") (pin "B28") (pinfunction "P_B28") (pintype "bidirectional"))
    )
    (net (code "109") (name "unconnected-(ST1AB-P-PadB8)") (class "Default")
      (node (ref "ST1") (pin "B8") (pinfunction "P_B8") (pintype "bidirectional"))
    )
    (net (code "110") (name "unconnected-(ST1AL-P-PadB17)") (class "Default")
      (node (ref "ST1") (pin "B17") (pinfunction "P_B17") (pintype "bidirectional"))
    )
    (net (code "111") (name "unconnected-(ST1AM-P-PadB26)") (class "Default")
      (node (ref "ST1") (pin "B26") (pinfunction "P_B26") (pintype "bidirectional"))
    )
    (net (code "112") (name "unconnected-(ST1AN-P-PadB15)") (class "Default")
      (node (ref "ST1") (pin "B15") (pinfunction "P_B15") (pintype "bidirectional"))
    )
    (net (code "113") (name "unconnected-(ST1AO-P-PadB18)") (class "Default")
      (node (ref "ST1") (pin "B18") (pinfunction "P_B18") (pintype "bidirectional"))
    )
    (net (code "114") (name "unconnected-(ST1AP-P-PadB6)") (class "Default")
      (node (ref "ST1") (pin "B6") (pinfunction "P_B6") (pintype "bidirectional"))
    )
    (net (code "115") (name "unconnected-(ST1AQ-P-PadB16)") (class "Default")
      (node (ref "ST1") (pin "B16") (pinfunction "P_B16") (pintype "bidirectional"))
    )
    (net (code "116") (name "unconnected-(ST1AU-P-PadA1)") (class "Default")
      (node (ref "ST1") (pin "A1") (pinfunction "P_A1") (pintype "bidirectional"))
    )
    (net (code "117") (name "unconnected-(ST1AY-P-PadB25)") (class "Default")
      (node (ref "ST1") (pin "B25") (pinfunction "P_B25") (pintype "bidirectional"))
    )
    (net (code "118") (name "unconnected-(ST1AZ-P-PadB24)") (class "Default")
      (node (ref "ST1") (pin "B24") (pinfunction "P_B24") (pintype "bidirectional"))
    )
    (net (code "119") (name "unconnected-(ST1BA-P-PadB23)") (class "Default")
      (node (ref "ST1") (pin "B23") (pinfunction "P_B23") (pintype "bidirectional"))
    )
    (net (code "120") (name "unconnected-(ST1BB-P-PadB22)") (class "Default")
      (node (ref "ST1") (pin "B22") (pinfunction "P_B22") (pintype "bidirectional"))
    )
    (net (code "121") (name "unconnected-(ST1BC-P-PadB21)") (class "Default")
      (node (ref "ST1") (pin "B21") (pinfunction "P_B21") (pintype "bidirectional"))
    )
    (net (code "122") (name "unconnected-(ST1BD-P-PadB4)") (class "Default")
      (node (ref "ST1") (pin "B4") (pinfunction "P_B4") (pintype "bidirectional"))
    )
    (net (code "123") (name "unconnected-(ST1BE-P-PadB12)") (class "Default")
      (node (ref "ST1") (pin "B12") (pinfunction "P_B12") (pintype "bidirectional"))
    )
    (net (code "124") (name "unconnected-(ST1BF-P-PadB11)") (class "Default")
      (node (ref "ST1") (pin "B11") (pinfunction "P_B11") (pintype "bidirectional"))
    )
    (net (code "125") (name "unconnected-(ST1BG-P-PadB30)") (class "Default")
      (node (ref "ST1") (pin "B30") (pinfunction "P_B30") (pintype "bidirectional"))
    )
    (net (code "126") (name "unconnected-(ST1BH-P-PadB19)") (class "Default")
      (node (ref "ST1") (pin "B19") (pinfunction "P_B19") (pintype "bidirectional"))
    )
    (net (code "127") (name "unconnected-(ST1BJ-P-PadB27)") (class "Default")
      (node (ref "ST1") (pin "B27") (pinfunction "P_B27") (pintype "bidirectional"))
    )
    (net (code "128") (name "unconnected-(ST1C-P-PadB3)") (class "Default")
      (node (ref "ST1") (pin "B3") (pinfunction "P_B3") (pintype "bidirectional"))
    )
    (net (code "129") (name "unconnected-(ST1E-P-PadB5)") (class "Default")
      (node (ref "ST1") (pin "B5") (pinfunction "P_B5") (pintype "bidirectional"))
    )
    (net (code "130") (name "unconnected-(ST1H-P-PadA21)") (class "Default")
      (node (ref "ST1") (pin "A21") (pinfunction "P_A21") (pintype "bidirectional"))
    )
    (net (code "131") (name "unconnected-(ST1I-P-PadA20)") (class "Default")
      (node (ref "ST1") (pin "A20") (pinfunction "P_A20") (pintype "bidirectional"))
    )
    (net (code "132") (name "unconnected-(ST1J-P-PadA19)") (class "Default")
      (node (ref "ST1") (pin "A19") (pinfunction "P_A19") (pintype "bidirectional"))
    )
    (net (code "133") (name "unconnected-(ST1K-P-PadA18)") (class "Default")
      (node (ref "ST1") (pin "A18") (pinfunction "P_A18") (pintype "bidirectional"))
    )
    (net (code "134") (name "unconnected-(ST1L-P-PadA17)") (class "Default")
      (node (ref "ST1") (pin "A17") (pinfunction "P_A17") (pintype "bidirectional"))
    )
    (net (code "135") (name "unconnected-(ST1M-P-PadA16)") (class "Default")
      (node (ref "ST1") (pin "A16") (pinfunction "P_A16") (pintype "bidirectional"))
    )
    (net (code "136") (name "unconnected-(ST1N-P-PadA15)") (class "Default")
      (node (ref "ST1") (pin "A15") (pinfunction "P_A15") (pintype "bidirectional"))
    )
    (net (code "137") (name "unconnected-(ST1O-P-PadA14)") (class "Default")
      (node (ref "ST1") (pin "A14") (pinfunction "P_A14") (pintype "bidirectional"))
    )
    (net (code "138") (name "unconnected-(ST1P-P-PadA13)") (class "Default")
      (node (ref "ST1") (pin "A13") (pinfunction "P_A13") (pintype "bidirectional"))
    )
    (net (code "139") (name "unconnected-(ST1Q-P-PadA12)") (class "Default")
      (node (ref "ST1") (pin "A12") (pinfunction "P_A12") (pintype "bidirectional"))
    )
  )
)
